# Board.net
KiCad netlist of a schematic drawn in Altium Designer
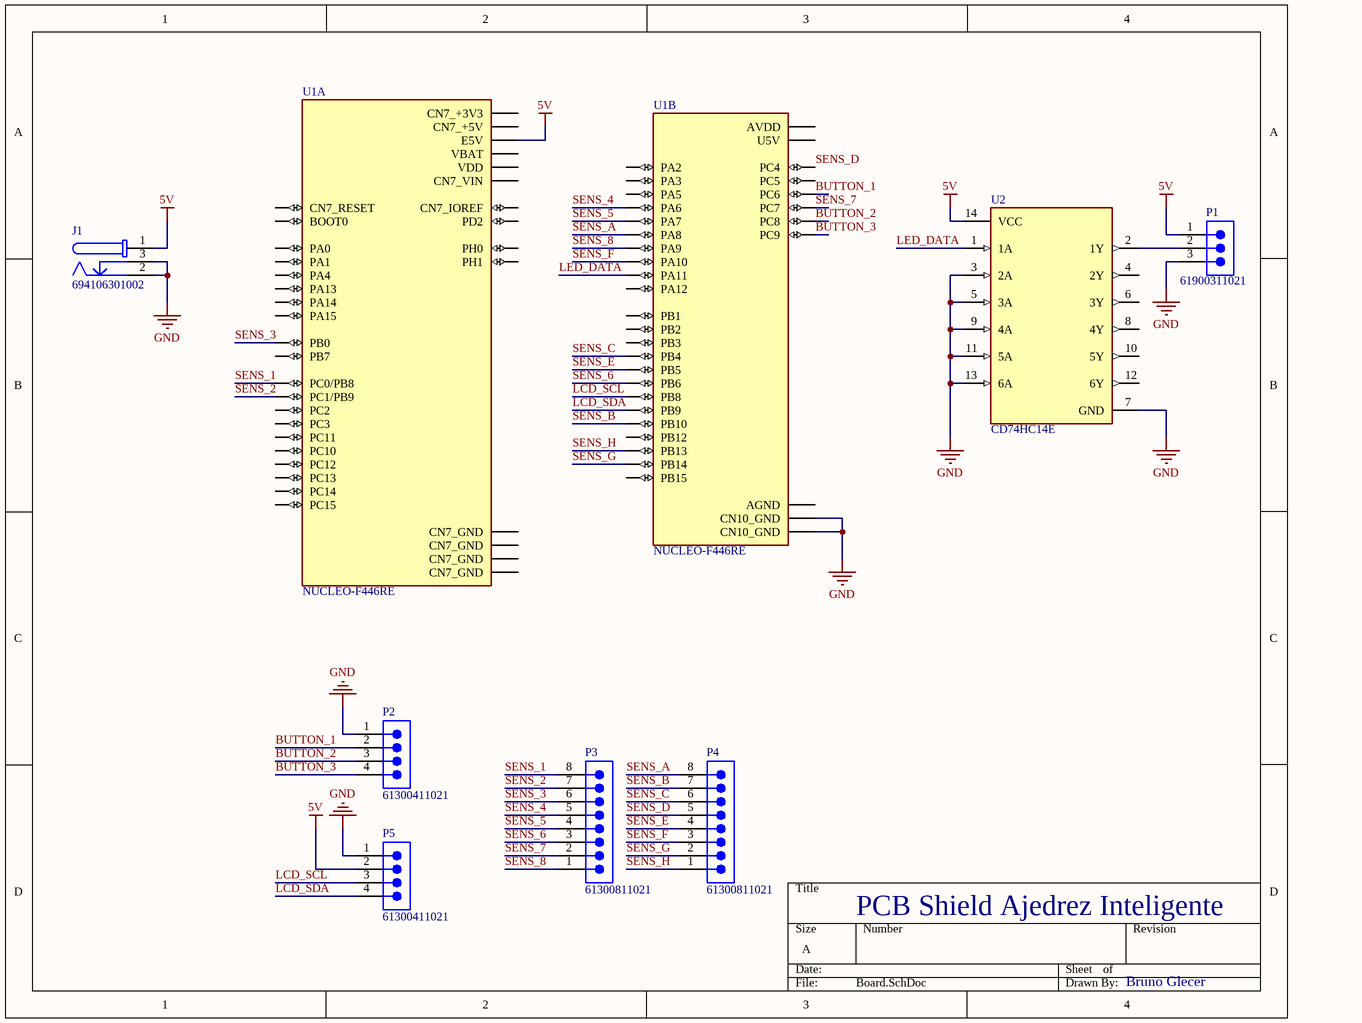
[diagram p0: Board.SchDoc]

(export (version "E")
  (design (tool "Eeschema 10.0.6"))
  (components
    (comp (ref "J1")
      (value "694106301002")
      (footprint "694106301002")
      (libsource (lib "Altium Content Vault") (part "DC Power Jack"))
    )
    (comp (ref "P1")
      (value "61900311021")
      (footprint "61900311021")
      (libsource (lib "Altium Content Vault") (part "Header_Male_1R_03P"))
    )
    (comp (ref "P2")
      (value "61300411021")
      (footprint "61300411021")
      (libsource (lib "Altium Content Vault") (part "Header_Male_1R_04P"))
    )
    (comp (ref "P3")
      (value "61300811021")
      (footprint "61300811021")
      (libsource (lib "Altium Content Vault") (part "Header_Male_1R_08P"))
    )
    (comp (ref "P4")
      (value "61300811021")
      (footprint "61300811021")
      (libsource (lib "Altium Content Vault") (part "Header_Male_1R_08P"))
    )
    (comp (ref "P5")
      (value "61300411021")
      (footprint "61300411021")
      (libsource (lib "Altium Content Vault") (part "Header_Male_1R_04P"))
    )
    (comp (ref "U1")
      (value "NUCLEO-F446RE")
      (footprint "MODULE_NUCLEO-F446RE")
      (libsource (lib "NUCLEO-F446RE") (part "NUCLEO-F446RE"))
    )
    (comp (ref "U2")
      (value "CD74HC14E")
      (footprint "FP-N0014A-MFG")
      (description "IC INVERTER SCHMITT 6CH 14DIP")
      (libsource (lib "Altium Content Vault") (part "9d66d67d3207619be613a833de1673a"))
    )
  )
  (nets
    (net (code "1") (name "/BUTTON_1") (class "Default")
      (node (ref "P2") (pin "2") (pinfunction "2_2") (pintype "passive"))
      (node (ref "U1") (pin "CN10_4") (pinfunction "PC6_CN10_4") (pintype "bidirectional"))
    )
    (net (code "2") (name "/BUTTON_2") (class "Default")
      (node (ref "P2") (pin "3") (pinfunction "3_3") (pintype "passive"))
      (node (ref "U1") (pin "CN10_2") (pinfunction "PC8_CN10_2") (pintype "bidirectional"))
    )
    (net (code "3") (name "/BUTTON_3") (class "Default")
      (node (ref "P2") (pin "4") (pinfunction "4_4") (pintype "passive"))
      (node (ref "U1") (pin "CN10_1") (pinfunction "PC9_CN10_1") (pintype "bidirectional"))
    )
    (net (code "4") (name "/LCD_SCL") (class "Default")
      (node (ref "P5") (pin "3") (pinfunction "3_3") (pintype "passive"))
      (node (ref "U1") (pin "CN10_3") (pinfunction "PB8_CN10_3") (pintype "bidirectional"))
    )
    (net (code "5") (name "/LCD_SDA") (class "Default")
      (node (ref "P5") (pin "4") (pinfunction "4_4") (pintype "passive"))
      (node (ref "U1") (pin "CN10_5") (pinfunction "PB9_CN10_5") (pintype "bidirectional"))
    )
    (net (code "6") (name "/LED_DATA") (class "Default")
      (node (ref "U1") (pin "CN10_14") (pinfunction "PA11_CN10_14") (pintype "bidirectional"))
      (node (ref "U2") (pin "1") (pinfunction "1A_1") (pintype "input"))
    )
    (net (code "7") (name "/SENS_1") (class "Default")
      (node (ref "P3") (pin "8") (pinfunction "8_8") (pintype "passive"))
      (node (ref "U1") (pin "CN7_38") (pinfunction "PC0/PB8_CN7_38") (pintype "bidirectional"))
    )
    (net (code "8") (name "/SENS_2") (class "Default")
      (node (ref "P3") (pin "7") (pinfunction "7_7") (pintype "passive"))
      (node (ref "U1") (pin "CN7_36") (pinfunction "PC1/PB9_CN7_36") (pintype "bidirectional"))
    )
    (net (code "9") (name "/SENS_3") (class "Default")
      (node (ref "P3") (pin "6") (pinfunction "6_6") (pintype "passive"))
      (node (ref "U1") (pin "CN7_34") (pinfunction "PB0_CN7_34") (pintype "bidirectional"))
    )
    (net (code "10") (name "/SENS_4") (class "Default")
      (node (ref "P3") (pin "5") (pinfunction "5_5") (pintype "passive"))
      (node (ref "U1") (pin "CN10_13") (pinfunction "PA6_CN10_13") (pintype "bidirectional"))
    )
    (net (code "11") (name "/SENS_5") (class "Default")
      (node (ref "P3") (pin "4") (pinfunction "4_4") (pintype "passive"))
      (node (ref "U1") (pin "CN10_15") (pinfunction "PA7_CN10_15") (pintype "bidirectional"))
    )
    (net (code "12") (name "/SENS_6") (class "Default")
      (node (ref "P3") (pin "3") (pinfunction "3_3") (pintype "passive"))
      (node (ref "U1") (pin "CN10_17") (pinfunction "PB6_CN10_17") (pintype "bidirectional"))
    )
    (net (code "13") (name "/SENS_7") (class "Default")
      (node (ref "P3") (pin "2") (pinfunction "2_2") (pintype "passive"))
      (node (ref "U1") (pin "CN10_19") (pinfunction "PC7_CN10_19") (pintype "bidirectional"))
    )
    (net (code "14") (name "/SENS_8") (class "Default")
      (node (ref "P3") (pin "1") (pinfunction "1_1") (pintype "passive"))
      (node (ref "U1") (pin "CN10_21") (pinfunction "PA9_CN10_21") (pintype "bidirectional"))
    )
    (net (code "15") (name "/SENS_A") (class "Default")
      (node (ref "P4") (pin "8") (pinfunction "8_8") (pintype "passive"))
      (node (ref "U1") (pin "CN10_23") (pinfunction "PA8_CN10_23") (pintype "bidirectional"))
    )
    (net (code "16") (name "/SENS_B") (class "Default")
      (node (ref "P4") (pin "7") (pinfunction "7_7") (pintype "passive"))
      (node (ref "U1") (pin "CN10_25") (pinfunction "PB10_CN10_25") (pintype "bidirectional"))
    )
    (net (code "17") (name "/SENS_C") (class "Default")
      (node (ref "P4") (pin "6") (pinfunction "6_6") (pintype "passive"))
      (node (ref "U1") (pin "CN10_27") (pinfunction "PB4_CN10_27") (pintype "bidirectional"))
    )
    (net (code "18") (name "/SENS_D") (class "Default")
      (node (ref "P4") (pin "5") (pinfunction "5_5") (pintype "passive"))
      (node (ref "U1") (pin "CN10_34") (pinfunction "PC4_CN10_34") (pintype "bidirectional"))
    )
    (net (code "19") (name "/SENS_E") (class "Default")
      (node (ref "P4") (pin "4") (pinfunction "4_4") (pintype "passive"))
      (node (ref "U1") (pin "CN10_29") (pinfunction "PB5_CN10_29") (pintype "bidirectional"))
    )
    (net (code "20") (name "/SENS_F") (class "Default")
      (node (ref "P4") (pin "3") (pinfunction "3_3") (pintype "passive"))
      (node (ref "U1") (pin "CN10_33") (pinfunction "PA10_CN10_33") (pintype "bidirectional"))
    )
    (net (code "21") (name "/SENS_G") (class "Default")
      (node (ref "P4") (pin "2") (pinfunction "2_2") (pintype "passive"))
      (node (ref "U1") (pin "CN10_28") (pinfunction "PB14_CN10_28") (pintype "bidirectional"))
    )
    (net (code "22") (name "/SENS_H") (class "Default")
      (node (ref "P4") (pin "1") (pinfunction "1_1") (pintype "passive"))
      (node (ref "U1") (pin "CN10_30") (pinfunction "PB13_CN10_30") (pintype "bidirectional"))
    )
    (net (code "23") (name "5V") (class "Default")
      (node (ref "J1") (pin "1") (pinfunction "1_1") (pintype "passive"))
      (node (ref "P1") (pin "1") (pinfunction "1_1") (pintype "passive"))
      (node (ref "P5") (pin "2") (pinfunction "2_2") (pintype "passive"))
      (node (ref "U1") (pin "CN7_6") (pinfunction "E5V_CN7_6") (pintype "power_in"))
      (node (ref "U2") (pin "14") (pinfunction "VCC_14") (pintype "power_in"))
    )
    (net (code "24") (name "GND") (class "Default")
      (node (ref "J1") (pin "2") (pinfunction "2_2") (pintype "passive"))
      (node (ref "J1") (pin "3") (pinfunction "3_3") (pintype "passive"))
      (node (ref "P1") (pin "3") (pinfunction "3_3") (pintype "passive"))
      (node (ref "P2") (pin "1") (pinfunction "1_1") (pintype "passive"))
      (node (ref "P5") (pin "1") (pinfunction "1_1") (pintype "passive"))
      (node (ref "U1") (pin "CN10_20") (pinfunction "CN10_GND_CN10_20") (pintype "power_in"))
      (node (ref "U1") (pin "CN10_9") (pinfunction "CN10_GND_CN10_9") (pintype "power_in"))
      (node (ref "U2") (pin "11") (pinfunction "5A_11") (pintype "input"))
      (node (ref "U2") (pin "13") (pinfunction "6A_13") (pintype "input"))
      (node (ref "U2") (pin "3") (pinfunction "2A_3") (pintype "input"))
      (node (ref "U2") (pin "5") (pinfunction "3A_5") (pintype "input"))
      (node (ref "U2") (pin "7") (pinfunction "GND_7") (pintype "power_in"))
      (node (ref "U2") (pin "9") (pinfunction "4A_9") (pintype "input"))
    )
    (net (code "25") (name "Net-(U2-1Y)") (class "Default")
      (node (ref "P1") (pin "2") (pinfunction "2_2") (pintype "passive"))
      (node (ref "U2") (pin "2") (pinfunction "1Y_2") (pintype "output"))
    )
    (net (code "26") (name "unconnected-(U1A-BOOT0-PadCN7_7)") (class "Default")
      (node (ref "U1") (pin "CN7_7") (pinfunction "BOOT0_CN7_7") (pintype "bidirectional"))
    )
    (net (code "27") (name "unconnected-(U1A-CN7_+3V3-PadCN7_16)") (class "Default")
      (node (ref "U1") (pin "CN7_16") (pinfunction "CN7_+3V3_CN7_16") (pintype "power_in"))
    )
    (net (code "28") (name "unconnected-(U1A-CN7_+5V-PadCN7_18)") (class "Default")
      (node (ref "U1") (pin "CN7_18") (pinfunction "CN7_+5V_CN7_18") (pintype "power_in"))
    )
    (net (code "29") (name "unconnected-(U1A-CN7_GND-PadCN7_8)") (class "Default")
      (node (ref "U1") (pin "CN7_8") (pinfunction "CN7_GND_CN7_8") (pintype "power_in"))
    )
    (net (code "30") (name "unconnected-(U1A-CN7_GND-PadCN7_19)") (class "Default")
      (node (ref "U1") (pin "CN7_19") (pinfunction "CN7_GND_CN7_19") (pintype "power_in"))
    )
    (net (code "31") (name "unconnected-(U1A-CN7_GND-PadCN7_20)") (class "Default")
      (node (ref "U1") (pin "CN7_20") (pinfunction "CN7_GND_CN7_20") (pintype "power_in"))
    )
    (net (code "32") (name "unconnected-(U1A-CN7_GND-PadCN7_22)") (class "Default")
      (node (ref "U1") (pin "CN7_22") (pinfunction "CN7_GND_CN7_22") (pintype "power_in"))
    )
    (net (code "33") (name "unconnected-(U1A-CN7_IOREF-PadCN7_12)") (class "Default")
      (node (ref "U1") (pin "CN7_12") (pinfunction "CN7_IOREF_CN7_12") (pintype "bidirectional"))
    )
    (net (code "34") (name "unconnected-(U1A-CN7_RESET-PadCN7_14)") (class "Default")
      (node (ref "U1") (pin "CN7_14") (pinfunction "CN7_RESET_CN7_14") (pintype "bidirectional"))
    )
    (net (code "35") (name "unconnected-(U1A-CN7_VIN-PadCN7_24)") (class "Default")
      (node (ref "U1") (pin "CN7_24") (pinfunction "CN7_VIN_CN7_24") (pintype "power_in"))
    )
    (net (code "36") (name "unconnected-(U1A-PA0-PadCN7_28)") (class "Default")
      (node (ref "U1") (pin "CN7_28") (pinfunction "PA0_CN7_28") (pintype "bidirectional"))
    )
    (net (code "37") (name "unconnected-(U1A-PA1-PadCN7_30)") (class "Default")
      (node (ref "U1") (pin "CN7_30") (pinfunction "PA1_CN7_30") (pintype "bidirectional"))
    )
    (net (code "38") (name "unconnected-(U1A-PA4-PadCN7_32)") (class "Default")
      (node (ref "U1") (pin "CN7_32") (pinfunction "PA4_CN7_32") (pintype "bidirectional"))
    )
    (net (code "39") (name "unconnected-(U1A-PA13-PadCN7_13)") (class "Default")
      (node (ref "U1") (pin "CN7_13") (pinfunction "PA13_CN7_13") (pintype "bidirectional"))
    )
    (net (code "40") (name "unconnected-(U1A-PA14-PadCN7_15)") (class "Default")
      (node (ref "U1") (pin "CN7_15") (pinfunction "PA14_CN7_15") (pintype "bidirectional"))
    )
    (net (code "41") (name "unconnected-(U1A-PA15-PadCN7_17)") (class "Default")
      (node (ref "U1") (pin "CN7_17") (pinfunction "PA15_CN7_17") (pintype "bidirectional"))
    )
    (net (code "42") (name "unconnected-(U1A-PB7-PadCN7_21)") (class "Default")
      (node (ref "U1") (pin "CN7_21") (pinfunction "PB7_CN7_21") (pintype "bidirectional"))
    )
    (net (code "43") (name "unconnected-(U1A-PC2-PadCN7_35)") (class "Default")
      (node (ref "U1") (pin "CN7_35") (pinfunction "PC2_CN7_35") (pintype "bidirectional"))
    )
    (net (code "44") (name "unconnected-(U1A-PC3-PadCN7_37)") (class "Default")
      (node (ref "U1") (pin "CN7_37") (pinfunction "PC3_CN7_37") (pintype "bidirectional"))
    )
    (net (code "45") (name "unconnected-(U1A-PC10-PadCN7_1)") (class "Default")
      (node (ref "U1") (pin "CN7_1") (pinfunction "PC10_CN7_1") (pintype "bidirectional"))
    )
    (net (code "46") (name "unconnected-(U1A-PC11-PadCN7_2)") (class "Default")
      (node (ref "U1") (pin "CN7_2") (pinfunction "PC11_CN7_2") (pintype "bidirectional"))
    )
    (net (code "47") (name "unconnected-(U1A-PC12-PadCN7_3)") (class "Default")
      (node (ref "U1") (pin "CN7_3") (pinfunction "PC12_CN7_3") (pintype "bidirectional"))
    )
    (net (code "48") (name "unconnected-(U1A-PC13-PadCN7_23)") (class "Default")
      (node (ref "U1") (pin "CN7_23") (pinfunction "PC13_CN7_23") (pintype "bidirectional"))
    )
    (net (code "49") (name "unconnected-(U1A-PC14-PadCN7_25)") (class "Default")
      (node (ref "U1") (pin "CN7_25") (pinfunction "PC14_CN7_25") (pintype "bidirectional"))
    )
    (net (code "50") (name "unconnected-(U1A-PC15-PadCN7_27)") (class "Default")
      (node (ref "U1") (pin "CN7_27") (pinfunction "PC15_CN7_27") (pintype "bidirectional"))
    )
    (net (code "51") (name "unconnected-(U1A-PD2-PadCN7_4)") (class "Default")
      (node (ref "U1") (pin "CN7_4") (pinfunction "PD2_CN7_4") (pintype "bidirectional"))
    )
    (net (code "52") (name "unconnected-(U1A-PH0-PadCN7_29)") (class "Default")
      (node (ref "U1") (pin "CN7_29") (pinfunction "PH0_CN7_29") (pintype "bidirectional"))
    )
    (net (code "53") (name "unconnected-(U1A-PH1-PadCN7_31)") (class "Default")
      (node (ref "U1") (pin "CN7_31") (pinfunction "PH1_CN7_31") (pintype "bidirectional"))
    )
    (net (code "54") (name "unconnected-(U1A-VBAT-PadCN7_33)") (class "Default")
      (node (ref "U1") (pin "CN7_33") (pinfunction "VBAT_CN7_33") (pintype "power_in"))
    )
    (net (code "55") (name "unconnected-(U1A-VDD-PadCN7_5)") (class "Default")
      (node (ref "U1") (pin "CN7_5") (pinfunction "VDD_CN7_5") (pintype "power_in"))
    )
    (net (code "56") (name "unconnected-(U1B-AGND-PadCN10_32)") (class "Default")
      (node (ref "U1") (pin "CN10_32") (pinfunction "AGND_CN10_32") (pintype "power_in"))
    )
    (net (code "57") (name "unconnected-(U1B-AVDD-PadCN10_7)") (class "Default")
      (node (ref "U1") (pin "CN10_7") (pinfunction "AVDD_CN10_7") (pintype "power_in"))
    )
    (net (code "58") (name "unconnected-(U1B-PA2-PadCN10_35)") (class "Default")
      (node (ref "U1") (pin "CN10_35") (pinfunction "PA2_CN10_35") (pintype "bidirectional"))
    )
    (net (code "59") (name "unconnected-(U1B-PA3-PadCN10_37)") (class "Default")
      (node (ref "U1") (pin "CN10_37") (pinfunction "PA3_CN10_37") (pintype "bidirectional"))
    )
    (net (code "60") (name "unconnected-(U1B-PA5-PadCN10_11)") (class "Default")
      (node (ref "U1") (pin "CN10_11") (pinfunction "PA5_CN10_11") (pintype "bidirectional"))
    )
    (net (code "61") (name "unconnected-(U1B-PA12-PadCN10_12)") (class "Default")
      (node (ref "U1") (pin "CN10_12") (pinfunction "PA12_CN10_12") (pintype "bidirectional"))
    )
    (net (code "62") (name "unconnected-(U1B-PB1-PadCN10_24)") (class "Default")
      (node (ref "U1") (pin "CN10_24") (pinfunction "PB1_CN10_24") (pintype "bidirectional"))
    )
    (net (code "63") (name "unconnected-(U1B-PB2-PadCN10_22)") (class "Default")
      (node (ref "U1") (pin "CN10_22") (pinfunction "PB2_CN10_22") (pintype "bidirectional"))
    )
    (net (code "64") (name "unconnected-(U1B-PB3-PadCN10_31)") (class "Default")
      (node (ref "U1") (pin "CN10_31") (pinfunction "PB3_CN10_31") (pintype "bidirectional"))
    )
    (net (code "65") (name "unconnected-(U1B-PB12-PadCN10_16)") (class "Default")
      (node (ref "U1") (pin "CN10_16") (pinfunction "PB12_CN10_16") (pintype "bidirectional"))
    )
    (net (code "66") (name "unconnected-(U1B-PB15-PadCN10_26)") (class "Default")
      (node (ref "U1") (pin "CN10_26") (pinfunction "PB15_CN10_26") (pintype "bidirectional"))
    )
    (net (code "67") (name "unconnected-(U1B-PC5-PadCN10_6)") (class "Default")
      (node (ref "U1") (pin "CN10_6") (pinfunction "PC5_CN10_6") (pintype "bidirectional"))
    )
    (net (code "68") (name "unconnected-(U1B-U5V-PadCN10_8)") (class "Default")
      (node (ref "U1") (pin "CN10_8") (pinfunction "U5V_CN10_8") (pintype "power_in"))
    )
    (net (code "69") (name "unconnected-(U2-2Y-Pad4)") (class "Default")
      (node (ref "U2") (pin "4") (pinfunction "2Y_4") (pintype "output"))
    )
    (net (code "70") (name "unconnected-(U2-3Y-Pad6)") (class "Default")
      (node (ref "U2") (pin "6") (pinfunction "3Y_6") (pintype "output"))
    )
    (net (code "71") (name "unconnected-(U2-4Y-Pad8)") (class "Default")
      (node (ref "U2") (pin "8") (pinfunction "4Y_8") (pintype "output"))
    )
    (net (code "72") (name "unconnected-(U2-5Y-Pad10)") (class "Default")
      (node (ref "U2") (pin "10") (pinfunction "5Y_10") (pintype "output"))
    )
    (net (code "73") (name "unconnected-(U2-6Y-Pad12)") (class "Default")
      (node (ref "U2") (pin "12") (pinfunction "6Y_12") (pintype "output"))
    )
  )
)
